# Wiring_Diagram_2020-10-04.net
KiCad netlist of a schematic drawn in EasyEDA
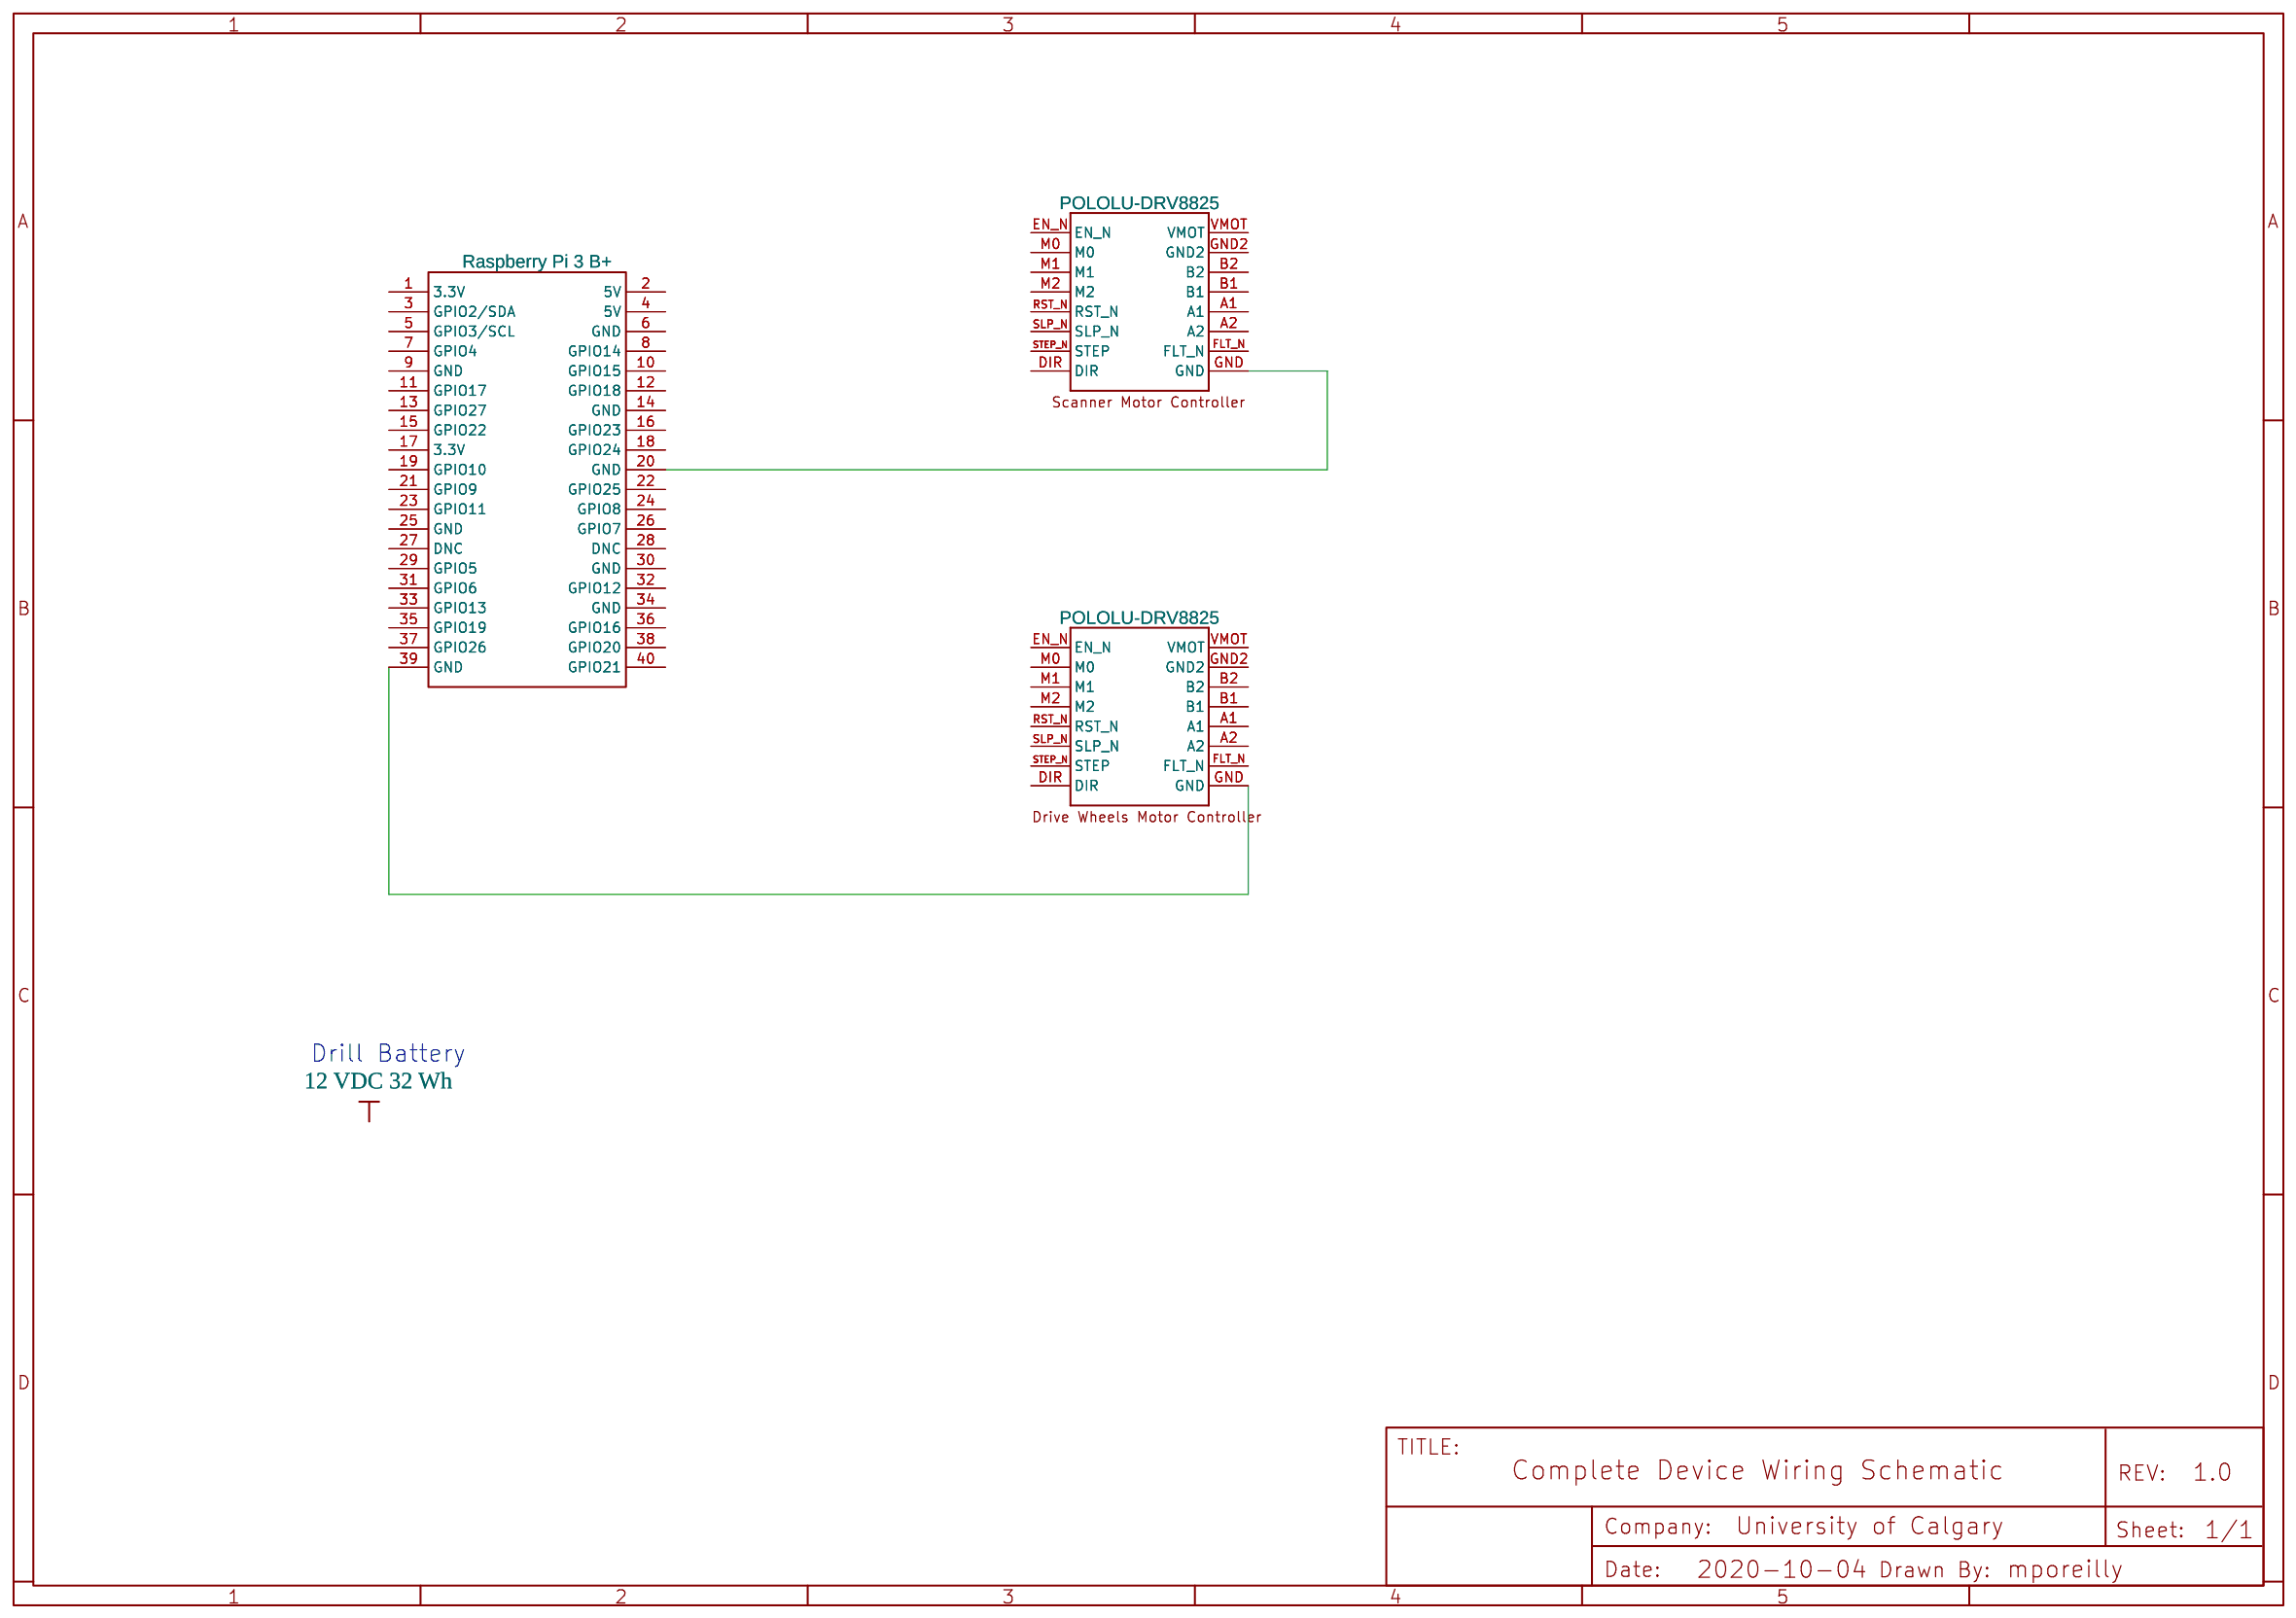
[diagram p0: schematic sheet]

(export (version "E")
  (design (tool "Eeschema 10.0.6"))
  (components
    (comp (ref "G$1") (value "POLOLU-DRV8825") (libsource (lib "") (part "POLOLU-DRV8825_1")))
    (comp (ref "G$2") (value "POLOLU-DRV8825") (libsource (lib "") (part "POLOLU-DRV8825")))
    (comp (ref "RPI1")
      (value "Raspberry Pi 3 B+")
      (fields
        (field (name "Manufacturer") "Raspberry Pi")
        (field (name "BOM_Manufacturer Part") "Raspberry Pi 3 - Model B+ - 1.4GHz Cortex-A53 with 1GB RAM")
        (field (name "BOM_Supplier Part") "3775")
      )
      (libsource (lib "") (part "Raspberry Pi 3 B+"))
    )
  )
  (nets
    (net (code "2") (name "Net-(G$1-PadGND)") (class "Default")
      (node (ref "G$1") (pin "GND") (pinfunction "GND_GND") (pintype "bidirectional"))
      (node (ref "RPI1") (pin "20") (pinfunction "GND_20") (pintype "unspecified"))
    )
    (net (code "3") (name "Net-(G$2-PadGND)") (class "Default")
      (node (ref "G$2") (pin "GND") (pinfunction "GND_GND") (pintype "bidirectional"))
      (node (ref "RPI1") (pin "39") (pinfunction "GND_39") (pintype "unspecified"))
    )
    (net (code "4") (name "unconnected-(G$1-PadA1)") (class "Default")
      (node (ref "G$1") (pin "A1") (pinfunction "A1_A1") (pintype "bidirectional"))
    )
    (net (code "5") (name "unconnected-(G$1-PadA2)") (class "Default")
      (node (ref "G$1") (pin "A2") (pinfunction "A2_A2") (pintype "bidirectional"))
    )
    (net (code "6") (name "unconnected-(G$1-PadB1)") (class "Default")
      (node (ref "G$1") (pin "B1") (pinfunction "B1_B1") (pintype "bidirectional"))
    )
    (net (code "7") (name "unconnected-(G$1-PadB2)") (class "Default")
      (node (ref "G$1") (pin "B2") (pinfunction "B2_B2") (pintype "bidirectional"))
    )
    (net (code "8") (name "unconnected-(G$1-PadDIR)") (class "Default")
      (node (ref "G$1") (pin "DIR") (pinfunction "DIR_DIR") (pintype "bidirectional"))
    )
    (net (code "9") (name "unconnected-(G$1-PadEN_N)") (class "Default")
      (node (ref "G$1") (pin "EN_N") (pinfunction "EN_N_EN_N") (pintype "bidirectional"))
    )
    (net (code "10") (name "unconnected-(G$1-PadFLT_N)") (class "Default")
      (node (ref "G$1") (pin "FLT_N") (pinfunction "FLT_N_FLT_N") (pintype "bidirectional"))
    )
    (net (code "11") (name "unconnected-(G$1-PadGND2)") (class "Default")
      (node (ref "G$1") (pin "GND2") (pinfunction "GND2_GND2") (pintype "bidirectional"))
    )
    (net (code "12") (name "unconnected-(G$1-PadM0)") (class "Default")
      (node (ref "G$1") (pin "M0") (pinfunction "M0_M0") (pintype "bidirectional"))
    )
    (net (code "13") (name "unconnected-(G$1-PadM1)") (class "Default")
      (node (ref "G$1") (pin "M1") (pinfunction "M1_M1") (pintype "bidirectional"))
    )
    (net (code "14") (name "unconnected-(G$1-PadM2)") (class "Default")
      (node (ref "G$1") (pin "M2") (pinfunction "M2_M2") (pintype "bidirectional"))
    )
    (net (code "15") (name "unconnected-(G$1-PadRST_N)") (class "Default")
      (node (ref "G$1") (pin "RST_N") (pinfunction "RST_N_RST_N") (pintype "bidirectional"))
    )
    (net (code "16") (name "unconnected-(G$1-PadSLP_N)") (class "Default")
      (node (ref "G$1") (pin "SLP_N") (pinfunction "SLP_N_SLP_N") (pintype "bidirectional"))
    )
    (net (code "17") (name "unconnected-(G$1-PadVMOT)") (class "Default")
      (node (ref "G$1") (pin "VMOT") (pinfunction "VMOT_VMOT") (pintype "bidirectional"))
    )
    (net (code "18") (name "unconnected-(G$1-STEP-PadSTEP_N)") (class "Default")
      (node (ref "G$1") (pin "STEP_N") (pinfunction "STEP_STEP_N") (pintype "bidirectional"))
    )
    (net (code "19") (name "unconnected-(G$2-PadA1)") (class "Default")
      (node (ref "G$2") (pin "A1") (pinfunction "A1_A1") (pintype "bidirectional"))
    )
    (net (code "20") (name "unconnected-(G$2-PadA2)") (class "Default")
      (node (ref "G$2") (pin "A2") (pinfunction "A2_A2") (pintype "bidirectional"))
    )
    (net (code "21") (name "unconnected-(G$2-PadB1)") (class "Default")
      (node (ref "G$2") (pin "B1") (pinfunction "B1_B1") (pintype "bidirectional"))
    )
    (net (code "22") (name "unconnected-(G$2-PadB2)") (class "Default")
      (node (ref "G$2") (pin "B2") (pinfunction "B2_B2") (pintype "bidirectional"))
    )
    (net (code "23") (name "unconnected-(G$2-PadDIR)") (class "Default")
      (node (ref "G$2") (pin "DIR") (pinfunction "DIR_DIR") (pintype "bidirectional"))
    )
    (net (code "24") (name "unconnected-(G$2-PadEN_N)") (class "Default")
      (node (ref "G$2") (pin "EN_N") (pinfunction "EN_N_EN_N") (pintype "bidirectional"))
    )
    (net (code "25") (name "unconnected-(G$2-PadFLT_N)") (class "Default")
      (node (ref "G$2") (pin "FLT_N") (pinfunction "FLT_N_FLT_N") (pintype "bidirectional"))
    )
    (net (code "26") (name "unconnected-(G$2-PadGND2)") (class "Default")
      (node (ref "G$2") (pin "GND2") (pinfunction "GND2_GND2") (pintype "bidirectional"))
    )
    (net (code "27") (name "unconnected-(G$2-PadM0)") (class "Default")
      (node (ref "G$2") (pin "M0") (pinfunction "M0_M0") (pintype "bidirectional"))
    )
    (net (code "28") (name "unconnected-(G$2-PadM1)") (class "Default")
      (node (ref "G$2") (pin "M1") (pinfunction "M1_M1") (pintype "bidirectional"))
    )
    (net (code "29") (name "unconnected-(G$2-PadM2)") (class "Default")
      (node (ref "G$2") (pin "M2") (pinfunction "M2_M2") (pintype "bidirectional"))
    )
    (net (code "30") (name "unconnected-(G$2-PadRST_N)") (class "Default")
      (node (ref "G$2") (pin "RST_N") (pinfunction "RST_N_RST_N") (pintype "bidirectional"))
    )
    (net (code "31") (name "unconnected-(G$2-PadSLP_N)") (class "Default")
      (node (ref "G$2") (pin "SLP_N") (pinfunction "SLP_N_SLP_N") (pintype "bidirectional"))
    )
    (net (code "32") (name "unconnected-(G$2-PadVMOT)") (class "Default")
      (node (ref "G$2") (pin "VMOT") (pinfunction "VMOT_VMOT") (pintype "bidirectional"))
    )
    (net (code "33") (name "unconnected-(G$2-STEP-PadSTEP_N)") (class "Default")
      (node (ref "G$2") (pin "STEP_N") (pinfunction "STEP_STEP_N") (pintype "bidirectional"))
    )
    (net (code "34") (name "unconnected-(RPI1-3.3V-Pad1)") (class "Default")
      (node (ref "RPI1") (pin "1") (pinfunction "3.3V_1") (pintype "passive"))
    )
    (net (code "35") (name "unconnected-(RPI1-3.3V-Pad17)") (class "Default")
      (node (ref "RPI1") (pin "17") (pinfunction "3.3V_17") (pintype "passive"))
    )
    (net (code "36") (name "unconnected-(RPI1-5V-Pad2)") (class "Default")
      (node (ref "RPI1") (pin "2") (pinfunction "5V_2") (pintype "passive"))
    )
    (net (code "37") (name "unconnected-(RPI1-5V-Pad4)") (class "Default")
      (node (ref "RPI1") (pin "4") (pinfunction "5V_4") (pintype "passive"))
    )
    (net (code "38") (name "unconnected-(RPI1-DNC-Pad27)") (class "Default")
      (node (ref "RPI1") (pin "27") (pinfunction "DNC_27") (pintype "unspecified"))
    )
    (net (code "39") (name "unconnected-(RPI1-DNC-Pad28)") (class "Default")
      (node (ref "RPI1") (pin "28") (pinfunction "DNC_28") (pintype "unspecified"))
    )
    (net (code "40") (name "unconnected-(RPI1-GND-Pad6)") (class "Default")
      (node (ref "RPI1") (pin "6") (pinfunction "GND_6") (pintype "unspecified"))
    )
    (net (code "41") (name "unconnected-(RPI1-GND-Pad9)") (class "Default")
      (node (ref "RPI1") (pin "9") (pinfunction "GND_9") (pintype "unspecified"))
    )
    (net (code "42") (name "unconnected-(RPI1-GND-Pad14)") (class "Default")
      (node (ref "RPI1") (pin "14") (pinfunction "GND_14") (pintype "unspecified"))
    )
    (net (code "43") (name "unconnected-(RPI1-GND-Pad25)") (class "Default")
      (node (ref "RPI1") (pin "25") (pinfunction "GND_25") (pintype "unspecified"))
    )
    (net (code "44") (name "unconnected-(RPI1-GND-Pad30)") (class "Default")
      (node (ref "RPI1") (pin "30") (pinfunction "GND_30") (pintype "unspecified"))
    )
    (net (code "45") (name "unconnected-(RPI1-GND-Pad34)") (class "Default")
      (node (ref "RPI1") (pin "34") (pinfunction "GND_34") (pintype "unspecified"))
    )
    (net (code "46") (name "unconnected-(RPI1-GPIO2{slash}SDA-Pad3)") (class "Default")
      (node (ref "RPI1") (pin "3") (pinfunction "GPIO2/SDA_3") (pintype "bidirectional"))
    )
    (net (code "47") (name "unconnected-(RPI1-GPIO3{slash}SCL-Pad5)") (class "Default")
      (node (ref "RPI1") (pin "5") (pinfunction "GPIO3/SCL_5") (pintype "bidirectional"))
    )
    (net (code "48") (name "unconnected-(RPI1-GPIO4-Pad7)") (class "Default")
      (node (ref "RPI1") (pin "7") (pinfunction "GPIO4_7") (pintype "bidirectional"))
    )
    (net (code "49") (name "unconnected-(RPI1-GPIO5-Pad29)") (class "Default")
      (node (ref "RPI1") (pin "29") (pinfunction "GPIO5_29") (pintype "bidirectional"))
    )
    (net (code "50") (name "unconnected-(RPI1-GPIO6-Pad31)") (class "Default")
      (node (ref "RPI1") (pin "31") (pinfunction "GPIO6_31") (pintype "bidirectional"))
    )
    (net (code "51") (name "unconnected-(RPI1-GPIO7-Pad26)") (class "Default")
      (node (ref "RPI1") (pin "26") (pinfunction "GPIO7_26") (pintype "bidirectional"))
    )
    (net (code "52") (name "unconnected-(RPI1-GPIO8-Pad24)") (class "Default")
      (node (ref "RPI1") (pin "24") (pinfunction "GPIO8_24") (pintype "bidirectional"))
    )
    (net (code "53") (name "unconnected-(RPI1-GPIO9-Pad21)") (class "Default")
      (node (ref "RPI1") (pin "21") (pinfunction "GPIO9_21") (pintype "bidirectional"))
    )
    (net (code "54") (name "unconnected-(RPI1-GPIO10-Pad19)") (class "Default")
      (node (ref "RPI1") (pin "19") (pinfunction "GPIO10_19") (pintype "bidirectional"))
    )
    (net (code "55") (name "unconnected-(RPI1-GPIO11-Pad23)") (class "Default")
      (node (ref "RPI1") (pin "23") (pinfunction "GPIO11_23") (pintype "bidirectional"))
    )
    (net (code "56") (name "unconnected-(RPI1-GPIO12-Pad32)") (class "Default")
      (node (ref "RPI1") (pin "32") (pinfunction "GPIO12_32") (pintype "bidirectional"))
    )
    (net (code "57") (name "unconnected-(RPI1-GPIO13-Pad33)") (class "Default")
      (node (ref "RPI1") (pin "33") (pinfunction "GPIO13_33") (pintype "bidirectional"))
    )
    (net (code "58") (name "unconnected-(RPI1-GPIO14-Pad8)") (class "Default")
      (node (ref "RPI1") (pin "8") (pinfunction "GPIO14_8") (pintype "bidirectional"))
    )
    (net (code "59") (name "unconnected-(RPI1-GPIO15-Pad10)") (class "Default")
      (node (ref "RPI1") (pin "10") (pinfunction "GPIO15_10") (pintype "bidirectional"))
    )
    (net (code "60") (name "unconnected-(RPI1-GPIO16-Pad36)") (class "Default")
      (node (ref "RPI1") (pin "36") (pinfunction "GPIO16_36") (pintype "bidirectional"))
    )
    (net (code "61") (name "unconnected-(RPI1-GPIO17-Pad11)") (class "Default")
      (node (ref "RPI1") (pin "11") (pinfunction "GPIO17_11") (pintype "bidirectional"))
    )
    (net (code "62") (name "unconnected-(RPI1-GPIO18-Pad12)") (class "Default")
      (node (ref "RPI1") (pin "12") (pinfunction "GPIO18_12") (pintype "bidirectional"))
    )
    (net (code "63") (name "unconnected-(RPI1-GPIO19-Pad35)") (class "Default")
      (node (ref "RPI1") (pin "35") (pinfunction "GPIO19_35") (pintype "bidirectional"))
    )
    (net (code "64") (name "unconnected-(RPI1-GPIO20-Pad38)") (class "Default")
      (node (ref "RPI1") (pin "38") (pinfunction "GPIO20_38") (pintype "bidirectional"))
    )
    (net (code "65") (name "unconnected-(RPI1-GPIO21-Pad40)") (class "Default")
      (node (ref "RPI1") (pin "40") (pinfunction "GPIO21_40") (pintype "bidirectional"))
    )
    (net (code "66") (name "unconnected-(RPI1-GPIO22-Pad15)") (class "Default")
      (node (ref "RPI1") (pin "15") (pinfunction "GPIO22_15") (pintype "bidirectional"))
    )
    (net (code "67") (name "unconnected-(RPI1-GPIO23-Pad16)") (class "Default")
      (node (ref "RPI1") (pin "16") (pinfunction "GPIO23_16") (pintype "bidirectional"))
    )
    (net (code "68") (name "unconnected-(RPI1-GPIO24-Pad18)") (class "Default")
      (node (ref "RPI1") (pin "18") (pinfunction "GPIO24_18") (pintype "bidirectional"))
    )
    (net (code "69") (name "unconnected-(RPI1-GPIO25-Pad22)") (class "Default")
      (node (ref "RPI1") (pin "22") (pinfunction "GPIO25_22") (pintype "bidirectional"))
    )
    (net (code "70") (name "unconnected-(RPI1-GPIO26-Pad37)") (class "Default")
      (node (ref "RPI1") (pin "37") (pinfunction "GPIO26_37") (pintype "bidirectional"))
    )
    (net (code "71") (name "unconnected-(RPI1-GPIO27-Pad13)") (class "Default")
      (node (ref "RPI1") (pin "13") (pinfunction "GPIO27_13") (pintype "bidirectional"))
    )
  )
)
